# SVR_REVTT_1_3.net
KiCad netlist of a schematic drawn in Altium Designer
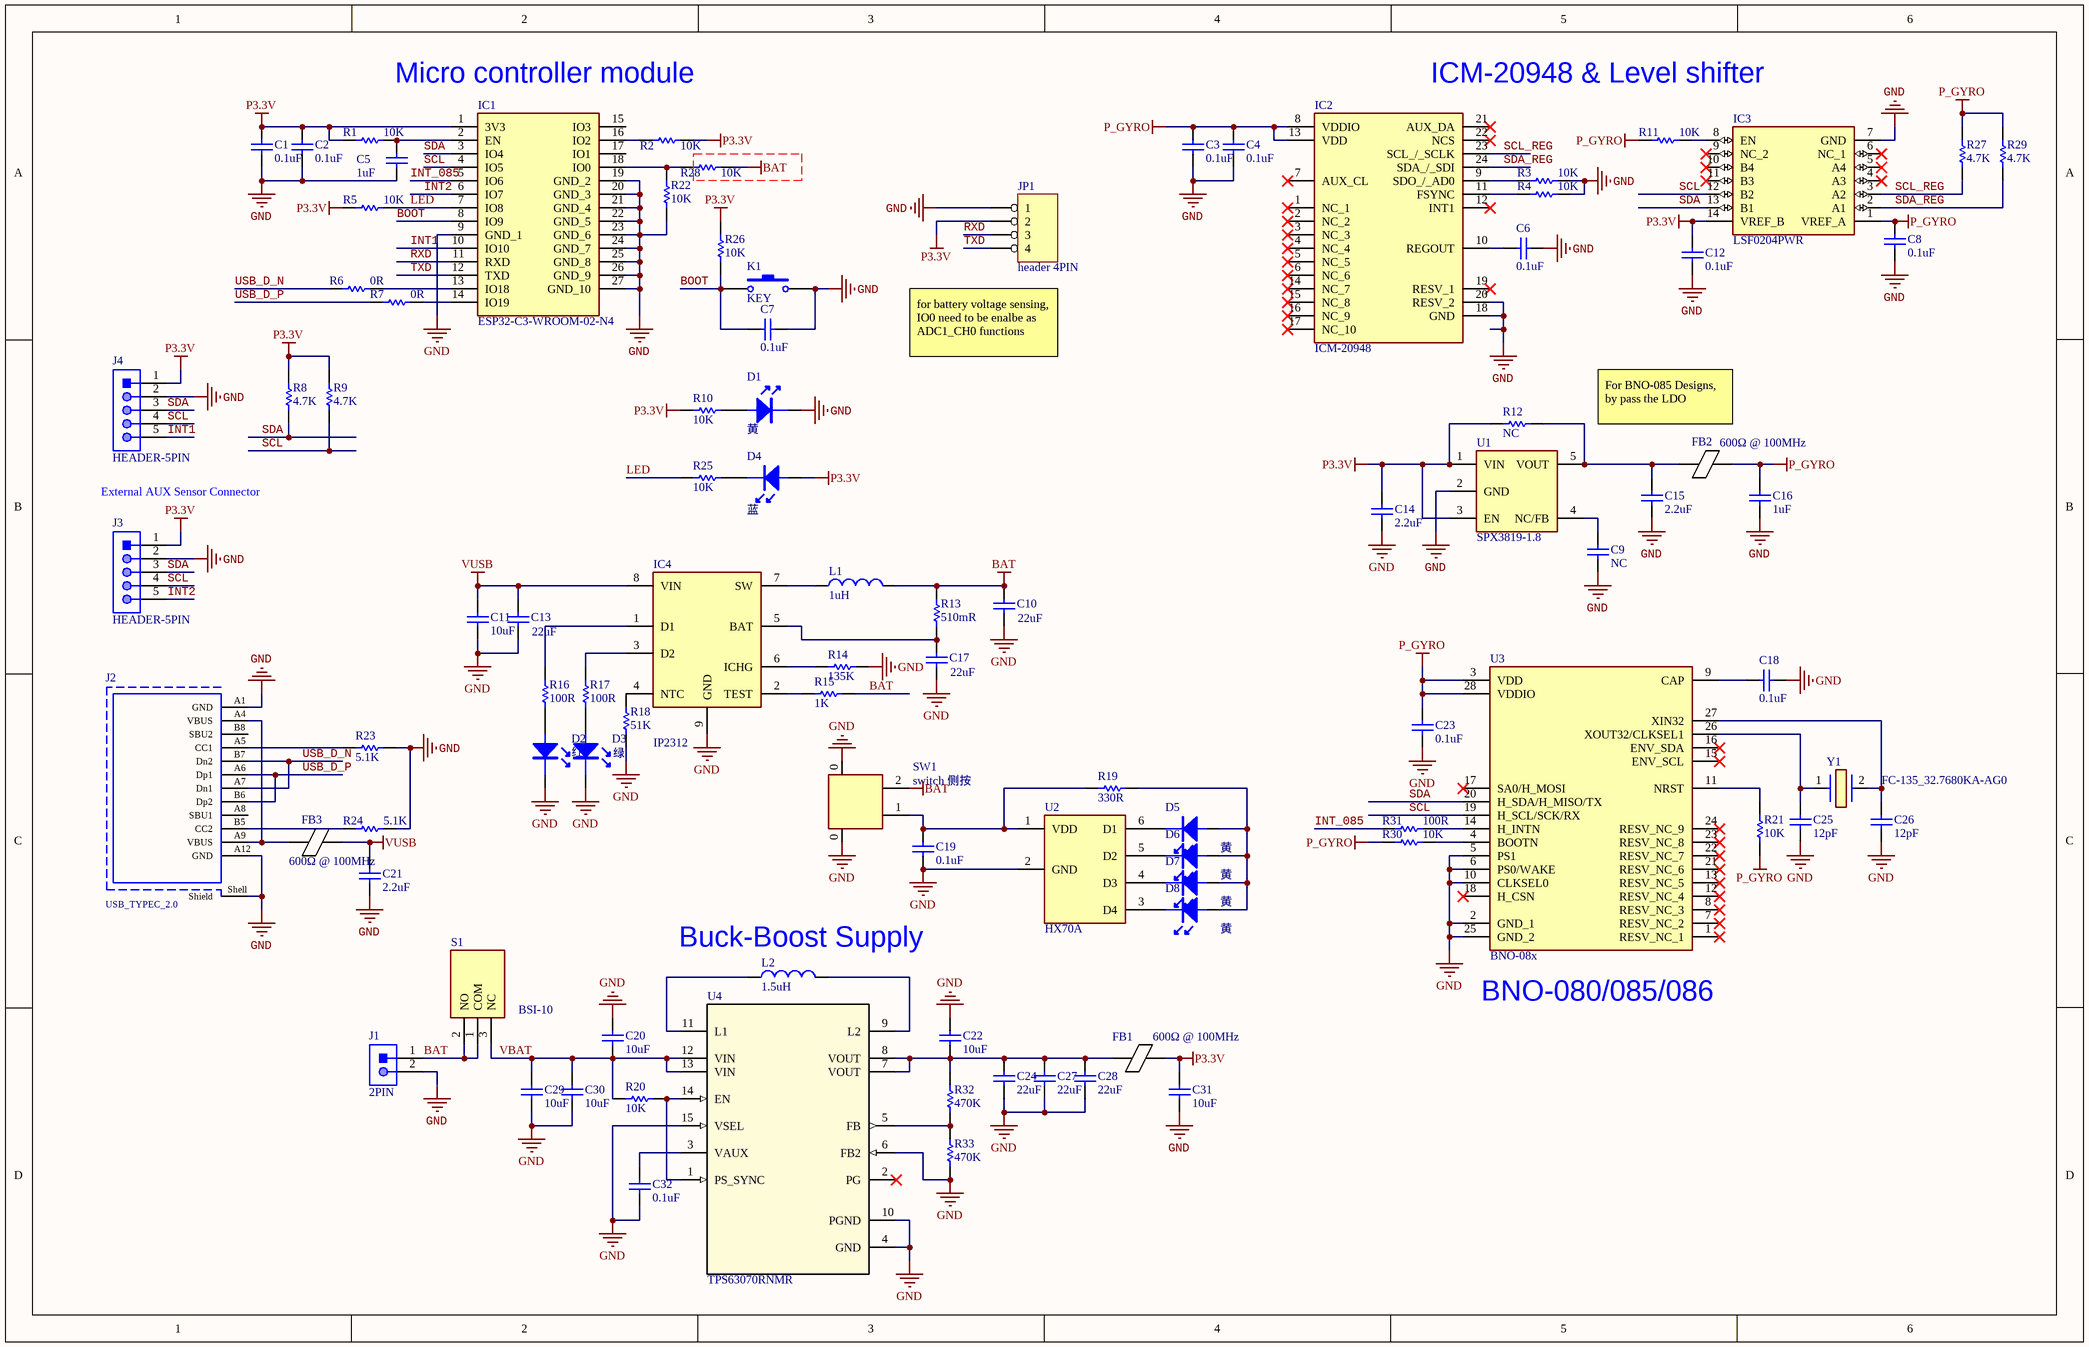
[diagram p0: SVR_REVTT_1.3.SchDoc]

(export (version "E")
  (design (tool "Eeschema 10.0.6"))
  (components
    (comp (ref "C1")
      (value "0.1uF")
      (footprint "0402L")
      (description "Capacitor")
      (fields (field (name "PUBLISHER") "Altium Limited"))
      (libsource (lib "My Footprint") (part "CAP"))
    )
    (comp (ref "C2")
      (value "0.1uF")
      (footprint "0402L")
      (description "Capacitor")
      (fields (field (name "PUBLISHER") "Altium Limited"))
      (libsource (lib "My Footprint") (part "CAP"))
    )
    (comp (ref "C3")
      (value "0.1uF")
      (footprint "0402L")
      (description "Capacitor")
      (fields (field (name "PUBLISHER") "Altium Limited"))
      (libsource (lib "My Footprint") (part "CAP"))
    )
    (comp (ref "C4")
      (value "0.1uF")
      (footprint "0402L")
      (description "Capacitor")
      (fields (field (name "PUBLISHER") "Altium Limited"))
      (libsource (lib "My Footprint") (part "CAP"))
    )
    (comp (ref "C5")
      (value "1uF")
      (footprint "0402L")
      (description "Capacitor")
      (fields (field (name "PUBLISHER") "Altium Limited"))
      (libsource (lib "My Footprint") (part "CAP"))
    )
    (comp (ref "C6")
      (value "0.1uF")
      (footprint "0402L")
      (description "Capacitor")
      (fields (field (name "PUBLISHER") "Altium Limited"))
      (libsource (lib "My Footprint") (part "CAP"))
    )
    (comp (ref "C7")
      (value "0.1uF")
      (footprint "0402L")
      (description "Capacitor")
      (fields (field (name "PUBLISHER") "Altium Limited"))
      (libsource (lib "My Footprint") (part "CAP"))
    )
    (comp (ref "C8")
      (value "0.1uF")
      (footprint "0402L")
      (description "Capacitor")
      (fields (field (name "PUBLISHER") "Altium Limited"))
      (libsource (lib "My Footprint") (part "CAP"))
    )
    (comp (ref "C9")
      (value "NC")
      (footprint "0603_C")
      (description "Capacitor")
      (fields (field (name "PUBLISHER") "Altium Limited"))
      (libsource (lib "My Footprint") (part "CAP"))
    )
    (comp (ref "C10")
      (value "22uF")
      (footprint "0805")
      (description "Capacitor")
      (fields (field (name "PUBLISHER") "Altium Limited"))
      (libsource (lib "My Footprint") (part "CAP"))
    )
    (comp (ref "C11")
      (value "10uF")
      (footprint "0805")
      (description "Capacitor")
      (fields (field (name "PUBLISHER") "Altium Limited"))
      (libsource (lib "My Footprint") (part "CAP"))
    )
    (comp (ref "C12")
      (value "0.1uF")
      (footprint "0402L")
      (description "Capacitor")
      (fields (field (name "PUBLISHER") "Altium Limited"))
      (libsource (lib "My Footprint") (part "CAP"))
    )
    (comp (ref "C13")
      (value "22uF")
      (footprint "0805")
      (description "Capacitor")
      (fields (field (name "PUBLISHER") "Altium Limited"))
      (libsource (lib "My Footprint") (part "CAP"))
    )
    (comp (ref "C14")
      (value "2.2uF")
      (footprint "0603_C")
      (description "Capacitor")
      (fields (field (name "PUBLISHER") "Altium Limited"))
      (libsource (lib "My Footprint") (part "CAP"))
    )
    (comp (ref "C15")
      (value "2.2uF")
      (footprint "0603_C")
      (description "Capacitor")
      (fields (field (name "PUBLISHER") "Altium Limited"))
      (libsource (lib "My Footprint") (part "CAP"))
    )
    (comp (ref "C16")
      (value "1uF")
      (footprint "0603_C")
      (description "Capacitor")
      (fields (field (name "PUBLISHER") "Altium Limited"))
      (libsource (lib "My Footprint") (part "CAP"))
    )
    (comp (ref "C17")
      (value "22uF")
      (footprint "0805")
      (description "Capacitor")
      (fields (field (name "PUBLISHER") "Altium Limited"))
      (libsource (lib "My Footprint") (part "CAP"))
    )
    (comp (ref "C18")
      (value "0.1uF")
      (footprint "0402L")
      (description "Capacitor")
      (fields (field (name "PUBLISHER") "Altium Limited"))
      (libsource (lib "My Footprint") (part "CAP"))
    )
    (comp (ref "C19")
      (value "0.1uF")
      (footprint "0402L")
      (description "Capacitor")
      (fields (field (name "PUBLISHER") "Altium Limited"))
      (libsource (lib "My Footprint") (part "CAP"))
    )
    (comp (ref "C20")
      (value "10uF")
      (footprint "0603_C")
      (description "Capacitor")
      (fields (field (name "PUBLISHER") "Altium Limited"))
      (libsource (lib "My Footprint") (part "CAP"))
    )
    (comp (ref "C21")
      (value "2.2uF")
      (footprint "0603_C")
      (description "Capacitor")
      (fields (field (name "PUBLISHER") "Altium Limited"))
      (libsource (lib "My Footprint") (part "CAP"))
    )
    (comp (ref "C22")
      (value "10uF")
      (footprint "0603_C")
      (description "Capacitor")
      (fields (field (name "PUBLISHER") "Altium Limited"))
      (libsource (lib "My Footprint") (part "CAP"))
    )
    (comp (ref "C23")
      (value "0.1uF")
      (footprint "0402L")
      (description "Capacitor")
      (fields (field (name "PUBLISHER") "Altium Limited"))
      (libsource (lib "My Footprint") (part "CAP"))
    )
    (comp (ref "C24")
      (value "22uF")
      (footprint "0805")
      (description "Capacitor")
      (fields (field (name "PUBLISHER") "Altium Limited"))
      (libsource (lib "My Footprint") (part "CAP"))
    )
    (comp (ref "C25")
      (value "12pF")
      (footprint "0402L")
      (description "Capacitor")
      (fields (field (name "PUBLISHER") "Altium Limited"))
      (libsource (lib "My Footprint") (part "CAP"))
    )
    (comp (ref "C26")
      (value "12pF")
      (footprint "0402L")
      (description "Capacitor")
      (fields (field (name "PUBLISHER") "Altium Limited"))
      (libsource (lib "My Footprint") (part "CAP"))
    )
    (comp (ref "C27")
      (value "22uF")
      (footprint "0805")
      (description "Capacitor")
      (fields (field (name "PUBLISHER") "Altium Limited"))
      (libsource (lib "My Footprint") (part "CAP"))
    )
    (comp (ref "C28")
      (value "22uF")
      (footprint "0805")
      (description "Capacitor")
      (fields (field (name "PUBLISHER") "Altium Limited"))
      (libsource (lib "My Footprint") (part "CAP"))
    )
    (comp (ref "C29")
      (value "10uF")
      (footprint "0805")
      (description "Capacitor")
      (fields (field (name "PUBLISHER") "Altium Limited"))
      (libsource (lib "My Footprint") (part "CAP"))
    )
    (comp (ref "C30")
      (value "10uF")
      (footprint "0805")
      (description "Capacitor")
      (fields (field (name "PUBLISHER") "Altium Limited"))
      (libsource (lib "My Footprint") (part "CAP"))
    )
    (comp (ref "C31")
      (value "10uF")
      (footprint "0805")
      (description "Capacitor")
      (fields (field (name "PUBLISHER") "Altium Limited"))
      (libsource (lib "My Footprint") (part "CAP"))
    )
    (comp (ref "C32")
      (value "0.1uF")
      (footprint "0402L")
      (description "Capacitor")
      (fields (field (name "PUBLISHER") "Altium Limited"))
      (libsource (lib "My Footprint") (part "CAP"))
    )
    (comp (ref "D1")
      (value "黄")
      (footprint "0603_LED")
      (description "LED 发光二极管")
      (libsource (lib "My Footprint") (part "LED"))
    )
    (comp (ref "D2")
      (value "红")
      (footprint "0603_LED")
      (description "LED 发光二极管")
      (libsource (lib "My Footprint") (part "LED"))
    )
    (comp (ref "D3")
      (value "绿")
      (footprint "0603_LED")
      (description "LED 发光二极管")
      (libsource (lib "My Footprint") (part "LED"))
    )
    (comp (ref "D4")
      (value "蓝")
      (footprint "0603_LED")
      (description "LED 发光二极管")
      (libsource (lib "") (part "LED_1"))
    )
    (comp (ref "D5")
      (value "黄")
      (footprint "0603_LED")
      (description "LED 发光二极管")
      (libsource (lib "My Footprint") (part "LED"))
    )
    (comp (ref "D6")
      (value "黄")
      (footprint "0603_LED")
      (description "LED 发光二极管")
      (libsource (lib "My Footprint") (part "LED"))
    )
    (comp (ref "D7")
      (value "黄")
      (footprint "0603_LED")
      (description "LED 发光二极管")
      (libsource (lib "My Footprint") (part "LED"))
    )
    (comp (ref "D8")
      (value "黄")
      (footprint "0603_LED")
      (description "LED 发光二极管")
      (libsource (lib "My Footprint") (part "LED"))
    )
    (comp (ref "FB1")
      (value "600Ω @ 100MHz")
      (footprint "0805")
      (description "磁珠 600Ω @ 100MHz")
      (libsource (lib "My Footprint") (part "FB"))
    )
    (comp (ref "FB2")
      (value "600Ω @ 100MHz")
      (footprint "0603")
      (description "磁珠 600Ω @ 100MHz")
      (libsource (lib "My Footprint") (part "FB"))
    )
    (comp (ref "FB3")
      (value "600Ω @ 100MHz")
      (footprint "0603")
      (description "磁珠 600Ω @ 100MHz")
      (libsource (lib "My Footprint") (part "FB"))
    )
    (comp (ref "IC1")
      (value "ESP32-C3-WROOM-02-N4")
      (footprint "SamacSys:ESP32C3WROOM02N4")
      (description "Integrated Circuit")
      (fields (field (name "MOUSER PART NUMBER") "356-ESP32C3WROOM02N4"))
      (libsource (lib "SamacSys") (part "ESP32-C3-WROOM-02-N4"))
    )
    (comp (ref "IC2")
      (value "ICM-20948")
      (footprint "SamacSys:QFN40P300X300X105-25N-D")
      (description "Integrated Circuit")
      (fields (field (name "MOUSER PART NUMBER") "410-ICM-20948"))
      (libsource (lib "SamacSys") (part "ICM-20948"))
    )
    (comp (ref "IC3")
      (value "LSF0204PWR")
      (footprint "SamacSys:SOP65P640X120-14N")
      (description "Integrated Circuit")
      (fields (field (name "MOUSER PART NUMBER") "595-LSF0204PWR"))
      (libsource (lib "SamacSys") (part "LSF0204PWR"))
    )
    (comp (ref "IC4")
      (value "IP2312")
      (footprint "SOIC-8N")
      (description "Integrated Circuit")
      (libsource (lib "SamacSys") (part "IP2312"))
    )
    (comp (ref "J1")
      (value "2PIN")
      (footprint "XH2.54-WI-2P")
      (libsource (lib "My Footprint") (part "HEADER 2PIN"))
    )
    (comp (ref "J2")
      (value "USB_TYPEC_2.0")
      (footprint "USB_TYPEC_2.0_Horizontal_SMT")
      (description "USB 3.1 Type C Receptacle WR-COM, Horizontal, SMT / THT")
      (fields (field (name "PART NUMBER") "632723300011") (field (name "PUBLISHER") "Wurth Elektronik"))
      (libsource (lib "RegenovoPcbLib") (part "USB_TYPEC_2.0"))
    )
    (comp (ref "J3")
      (value "HEADER-5PIN")
      (footprint "HEADER_5P_1.25_RT")
      (libsource (lib "My Footprint") (part "HEADER-5PIN"))
    )
    (comp (ref "J4")
      (value "HEADER-5PIN")
      (footprint "HEADER_5P_1.25_RT")
      (libsource (lib "My Footprint") (part "HEADER-5PIN"))
    )
    (comp (ref "JP1")
      (value "header 4PIN")
      (footprint "header4")
      (libsource (lib "My Footprint") (part "HEADER 4"))
    )
    (comp (ref "K1")
      (value "KEY")
      (footprint "KEY_2")
      (description "Switch")
      (fields (field (name "PUBLISHER") "Altium Limited"))
      (libsource (lib "My Footprint") (part "KEY_2"))
    )
    (comp (ref "L1")
      (value "1uH")
      (footprint "Inductor  SLO0650")
      (description "电感")
      (fields (field (name "Comment") "INDUCTOR") (field (name "PUBLISHER") "Altium Limited"))
      (libsource (lib "RegenovoPcbLib") (part "INDUCTOR"))
    )
    (comp (ref "L2")
      (value "1.5uH")
      (footprint "Inductor  SMNR4020")
      (description "电感")
      (fields (field (name "Comment") "INDUCTOR") (field (name "PUBLISHER") "Altium Limited"))
      (libsource (lib "RegenovoPcbLib") (part "INDUCTOR"))
    )
    (comp (ref "R1")
      (value "10K")
      (footprint "0402L")
      (description "Resistor")
      (fields (field (name "PUBLISHER") "Altium Limited"))
      (libsource (lib "My Footprint") (part "RES"))
    )
    (comp (ref "R2")
      (value "10K")
      (footprint "0402L")
      (description "Resistor")
      (fields (field (name "PUBLISHER") "Altium Limited"))
      (libsource (lib "My Footprint") (part "RES"))
    )
    (comp (ref "R3")
      (value "10K")
      (footprint "0402L")
      (description "Resistor")
      (fields (field (name "PUBLISHER") "Altium Limited"))
      (libsource (lib "My Footprint") (part "RES"))
    )
    (comp (ref "R4")
      (value "10K")
      (footprint "0402L")
      (description "Resistor")
      (fields (field (name "PUBLISHER") "Altium Limited"))
      (libsource (lib "My Footprint") (part "RES"))
    )
    (comp (ref "R5")
      (value "10K")
      (footprint "0402L")
      (description "Resistor")
      (fields (field (name "PUBLISHER") "Altium Limited"))
      (libsource (lib "My Footprint") (part "RES"))
    )
    (comp (ref "R6")
      (value "0R")
      (footprint "0402L")
      (description "Resistor")
      (fields (field (name "PUBLISHER") "Altium Limited"))
      (libsource (lib "My Footprint") (part "RES"))
    )
    (comp (ref "R7")
      (value "0R")
      (footprint "0402L")
      (description "Resistor")
      (fields (field (name "PUBLISHER") "Altium Limited"))
      (libsource (lib "My Footprint") (part "RES"))
    )
    (comp (ref "R8")
      (value "4.7K")
      (footprint "0402L")
      (description "Resistor")
      (fields (field (name "PUBLISHER") "Altium Limited"))
      (libsource (lib "My Footprint") (part "RES"))
    )
    (comp (ref "R9")
      (value "4.7K")
      (footprint "0402L")
      (description "Resistor")
      (fields (field (name "PUBLISHER") "Altium Limited"))
      (libsource (lib "My Footprint") (part "RES"))
    )
    (comp (ref "R10")
      (value "10K")
      (footprint "0402L")
      (description "Resistor")
      (fields (field (name "PUBLISHER") "Altium Limited"))
      (libsource (lib "My Footprint") (part "RES"))
    )
    (comp (ref "R11")
      (value "10K")
      (footprint "0402L")
      (description "Resistor")
      (fields (field (name "PUBLISHER") "Altium Limited"))
      (libsource (lib "My Footprint") (part "RES"))
    )
    (comp (ref "R12")
      (value "NC")
      (footprint "0603")
      (description "Resistor")
      (fields (field (name "PUBLISHER") "Altium Limited"))
      (libsource (lib "My Footprint") (part "RES"))
    )
    (comp (ref "R13")
      (value "510mR")
      (footprint "0603L")
      (description "Resistor")
      (fields (field (name "PUBLISHER") "Altium Limited"))
      (libsource (lib "My Footprint") (part "RES"))
    )
    (comp (ref "R14")
      (value "135K")
      (footprint "0402L")
      (description "Resistor")
      (fields (field (name "PUBLISHER") "Altium Limited"))
      (libsource (lib "My Footprint") (part "RES"))
    )
    (comp (ref "R15")
      (value "1K")
      (footprint "0402L")
      (description "Resistor")
      (fields (field (name "PUBLISHER") "Altium Limited"))
      (libsource (lib "My Footprint") (part "RES"))
    )
    (comp (ref "R16")
      (value "100R")
      (footprint "0402L")
      (description "Resistor")
      (fields (field (name "PUBLISHER") "Altium Limited"))
      (libsource (lib "My Footprint") (part "RES"))
    )
    (comp (ref "R17")
      (value "100R")
      (footprint "0402L")
      (description "Resistor")
      (fields (field (name "PUBLISHER") "Altium Limited"))
      (libsource (lib "My Footprint") (part "RES"))
    )
    (comp (ref "R18")
      (value "51K")
      (footprint "0402L")
      (description "Resistor")
      (fields (field (name "PUBLISHER") "Altium Limited"))
      (libsource (lib "My Footprint") (part "RES"))
    )
    (comp (ref "R19")
      (value "330R")
      (footprint "0603_R")
      (description "Resistor")
      (fields (field (name "PUBLISHER") "Altium Limited"))
      (libsource (lib "My Footprint") (part "RES"))
    )
    (comp (ref "R20")
      (value "10K")
      (footprint "0402L")
      (description "Resistor")
      (fields (field (name "PUBLISHER") "Altium Limited"))
      (libsource (lib "My Footprint") (part "RES"))
    )
    (comp (ref "R21")
      (value "10K")
      (footprint "0402L")
      (description "Resistor")
      (fields (field (name "PUBLISHER") "Altium Limited"))
      (libsource (lib "My Footprint") (part "RES"))
    )
    (comp (ref "R22")
      (value "10K")
      (footprint "0402L")
      (description "Resistor")
      (fields (field (name "PUBLISHER") "Altium Limited"))
      (libsource (lib "My Footprint") (part "RES"))
    )
    (comp (ref "R23")
      (value "5.1K")
      (footprint "0402L")
      (description "Resistor")
      (fields (field (name "PUBLISHER") "Altium Limited"))
      (libsource (lib "My Footprint") (part "RES"))
    )
    (comp (ref "R24")
      (value "5.1K")
      (footprint "0402L")
      (description "Resistor")
      (fields (field (name "PUBLISHER") "Altium Limited"))
      (libsource (lib "My Footprint") (part "RES"))
    )
    (comp (ref "R25")
      (value "10K")
      (footprint "0402L")
      (description "Resistor")
      (fields (field (name "PUBLISHER") "Altium Limited"))
      (libsource (lib "My Footprint") (part "RES"))
    )
    (comp (ref "R26")
      (value "10K")
      (footprint "0402L")
      (description "Resistor")
      (fields (field (name "PUBLISHER") "Altium Limited"))
      (libsource (lib "My Footprint") (part "RES"))
    )
    (comp (ref "R27")
      (value "4.7K")
      (footprint "0402L")
      (description "Resistor")
      (fields (field (name "PUBLISHER") "Altium Limited"))
      (libsource (lib "My Footprint") (part "RES"))
    )
    (comp (ref "R28")
      (value "10K")
      (footprint "0402L")
      (description "Resistor")
      (fields (field (name "PUBLISHER") "Altium Limited"))
      (libsource (lib "My Footprint") (part "RES"))
    )
    (comp (ref "R29")
      (value "4.7K")
      (footprint "0402L")
      (description "Resistor")
      (fields (field (name "PUBLISHER") "Altium Limited"))
      (libsource (lib "My Footprint") (part "RES"))
    )
    (comp (ref "R30")
      (value "10K")
      (footprint "0402L")
      (description "Resistor")
      (fields (field (name "PUBLISHER") "Altium Limited"))
      (libsource (lib "My Footprint") (part "RES"))
    )
    (comp (ref "R31")
      (value "100R")
      (footprint "0402L")
      (description "Resistor")
      (fields (field (name "PUBLISHER") "Altium Limited"))
      (libsource (lib "My Footprint") (part "RES"))
    )
    (comp (ref "R32")
      (value "470K")
      (footprint "0402L")
      (description "Resistor")
      (fields (field (name "PUBLISHER") "Altium Limited"))
      (libsource (lib "My Footprint") (part "RES"))
    )
    (comp (ref "R33")
      (value "470K")
      (footprint "0402L")
      (description "Resistor")
      (fields (field (name "PUBLISHER") "Altium Limited"))
      (libsource (lib "My Footprint") (part "RES"))
    )
    (comp (ref "S1")
      (value "BSI-10")
      (footprint "BSI10")
      (description "Switch")
      (libsource (lib "SamacSys") (part "BSI-10"))
    )
    (comp (ref "SW1")
      (value "switch 侧按")
      (footprint "TSW 3*6*4.3-S-W")
      (libsource (lib "SamacSys") (part "switch 侧按"))
    )
    (comp (ref "U1")
      (value "SPX3819-1.8")
      (footprint "SOT-23-5")
      (libsource (lib "My Footprint") (part "ADP150"))
    )
    (comp (ref "U2")
      (value "HX70A")
      (footprint "SOT95P250X110-6N")
      (description "单节锂电池电量指示芯片")
      (libsource (lib "SamacSys") (part "HX70A"))
    )
    (comp (ref "U3")
      (value "BNO-08x")
      (footprint "SamacSys:BNO085")
      (description "Accelerometer")
      (fields (field (name "MANUFACTURER_PART_NUMBER") "BNO085"))
      (libsource (lib "SamacSys") (part "BNO085"))
    )
    (comp (ref "U4")
      (value "TPS63070RNMR")
      (footprint "RNM0015A")
      (description "Imported")
      (fields (field (name "MANUFACTURER") "Texas Instruments"))
      (libsource (lib "SamacSys") (part "TPS63070RNMR"))
    )
    (comp (ref "Y1")
      (value "FC-135_32.7680KA-AG0")
      (footprint "SamacSys:FC135327680KAAG0")
      (description "Crystal or Oscillator")
      (fields
        (field (name "MANUFACTURER_PART_NUMBER") "FC-135 32.7680KA-AG0")
        (field (name "MOUSER PART NUMBER") "732-FC135-32.76KAAG0")
      )
      (libsource (lib "SamacSys") (part "FC-135_32.7680KA-AG0"))
    )
  )
  (nets
    (net (code "1") (name "/BOOT") (class "Default")
      (node (ref "C7") (pin "1") (pinfunction "1_1") (pintype "passive"))
      (node (ref "IC1") (pin "8") (pinfunction "IO9_8") (pintype "passive"))
      (node (ref "K1") (pin "1") (pinfunction "1_1") (pintype "passive"))
      (node (ref "R26") (pin "1") (pinfunction "1_1") (pintype "passive"))
    )
    (net (code "2") (name "/INT1") (class "Default")
      (node (ref "IC1") (pin "10") (pinfunction "IO10_10") (pintype "passive"))
      (node (ref "J4") (pin "5") (pinfunction "5_5") (pintype "passive"))
    )
    (net (code "3") (name "/INT2") (class "Default")
      (node (ref "IC1") (pin "6") (pinfunction "IO7_6") (pintype "passive"))
      (node (ref "J3") (pin "5") (pinfunction "5_5") (pintype "passive"))
    )
    (net (code "4") (name "/INT_085") (class "Default")
      (node (ref "IC1") (pin "5") (pinfunction "IO6_5") (pintype "passive"))
      (node (ref "R31") (pin "1") (pinfunction "1_1") (pintype "passive"))
    )
    (net (code "5") (name "/LED") (class "Default")
      (node (ref "IC1") (pin "7") (pinfunction "IO8_7") (pintype "passive"))
      (node (ref "R25") (pin "1") (pinfunction "1_1") (pintype "passive"))
      (node (ref "R5") (pin "2") (pinfunction "2_2") (pintype "passive"))
    )
    (net (code "6") (name "/RXD") (class "Default")
      (node (ref "IC1") (pin "11") (pinfunction "RXD_11") (pintype "passive"))
      (node (ref "JP1") (pin "3") (pinfunction "3_3") (pintype "passive"))
    )
    (net (code "7") (name "/SCL") (class "Default")
      (node (ref "IC1") (pin "4") (pinfunction "IO5_4") (pintype "passive"))
      (node (ref "IC3") (pin "12") (pinfunction "B2_12") (pintype "bidirectional"))
      (node (ref "J3") (pin "4") (pinfunction "4_4") (pintype "passive"))
      (node (ref "J4") (pin "4") (pinfunction "4_4") (pintype "passive"))
      (node (ref "R9") (pin "1") (pinfunction "1_1") (pintype "passive"))
      (node (ref "U3") (pin "19") (pinfunction "H_SCL/SCK/RX_19") (pintype "passive"))
    )
    (net (code "8") (name "/SCL_REG") (class "Default")
      (node (ref "IC2") (pin "23") (pinfunction "SCL_/_SCLK_23") (pintype "passive"))
      (node (ref "IC3") (pin "3") (pinfunction "A2_3") (pintype "bidirectional"))
      (node (ref "R27") (pin "1") (pinfunction "1_1") (pintype "passive"))
    )
    (net (code "9") (name "/SDA") (class "Default")
      (node (ref "IC1") (pin "3") (pinfunction "IO4_3") (pintype "passive"))
      (node (ref "IC3") (pin "13") (pinfunction "B1_13") (pintype "bidirectional"))
      (node (ref "J3") (pin "3") (pinfunction "3_3") (pintype "passive"))
      (node (ref "J4") (pin "3") (pinfunction "3_3") (pintype "passive"))
      (node (ref "R8") (pin "1") (pinfunction "1_1") (pintype "passive"))
      (node (ref "U3") (pin "20") (pinfunction "H_SDA/H_MISO/TX_20") (pintype "passive"))
    )
    (net (code "10") (name "/SDA_REG") (class "Default")
      (node (ref "IC2") (pin "24") (pinfunction "SDA_/_SDI_24") (pintype "passive"))
      (node (ref "IC3") (pin "2") (pinfunction "A1_2") (pintype "bidirectional"))
      (node (ref "R29") (pin "1") (pinfunction "1_1") (pintype "passive"))
    )
    (net (code "11") (name "/TXD") (class "Default")
      (node (ref "IC1") (pin "12") (pinfunction "TXD_12") (pintype "passive"))
      (node (ref "JP1") (pin "4") (pinfunction "4_4") (pintype "passive"))
    )
    (net (code "12") (name "/USB_D_N") (class "Default")
      (node (ref "J2") (pin "A7") (pinfunction "Dn1_A7") (pintype "passive"))
      (node (ref "J2") (pin "B7") (pinfunction "Dn2_B7") (pintype "passive"))
      (node (ref "R6") (pin "1") (pinfunction "1_1") (pintype "passive"))
    )
    (net (code "13") (name "/USB_D_P") (class "Default")
      (node (ref "J2") (pin "A6") (pinfunction "Dp1_A6") (pintype "passive"))
      (node (ref "J2") (pin "B6") (pinfunction "Dp2_B6") (pintype "passive"))
      (node (ref "R7") (pin "1") (pinfunction "1_1") (pintype "passive"))
    )
    (net (code "14") (name "/VBAT") (class "Default")
      (node (ref "C20") (pin "1") (pinfunction "1_1") (pintype "passive"))
      (node (ref "C29") (pin "2") (pinfunction "2_2") (pintype "passive"))
      (node (ref "C30") (pin "2") (pinfunction "2_2") (pintype "passive"))
      (node (ref "R20") (pin "1") (pinfunction "1_1") (pintype "passive"))
      (node (ref "S1") (pin "3") (pinfunction "NC_3") (pintype "passive"))
      (node (ref "U4") (pin "12") (pinfunction "VIN_12") (pintype "power_in"))
      (node (ref "U4") (pin "13") (pinfunction "VIN_13") (pintype "power_in"))
    )
    (net (code "15") (name "BAT") (class "Default")
      (node (ref "C10") (pin "2") (pinfunction "2_2") (pintype "passive"))
      (node (ref "J1") (pin "1") (pinfunction "1_1") (pintype "passive"))
      (node (ref "L1") (pin "2") (pinfunction "2_2") (pintype "passive"))
      (node (ref "R13") (pin "2") (pinfunction "2_2") (pintype "passive"))
      (node (ref "R15") (pin "2") (pinfunction "2_2") (pintype "passive"))
      (node (ref "R28") (pin "2") (pinfunction "2_2") (pintype "passive"))
      (node (ref "S1") (pin "1") (pinfunction "COM_1") (pintype "passive"))
      (node (ref "S1") (pin "2") (pinfunction "NO_2") (pintype "passive"))
      (node (ref "SW1") (pin "2") (pinfunction "2_2") (pintype "passive"))
    )
    (net (code "16") (name "GND") (class "Default")
      (node (ref "C1") (pin "1") (pinfunction "1_1") (pintype "passive"))
      (node (ref "C10") (pin "1") (pinfunction "1_1") (pintype "passive"))
      (node (ref "C11") (pin "1") (pinfunction "1_1") (pintype "passive"))
      (node (ref "C12") (pin "2") (pinfunction "2_2") (pintype "passive"))
      (node (ref "C13") (pin "1") (pinfunction "1_1") (pintype "passive"))
      (node (ref "C14") (pin "1") (pinfunction "1_1") (pintype "passive"))
      (node (ref "C15") (pin "1") (pinfunction "1_1") (pintype "passive"))
      (node (ref "C16") (pin "1") (pinfunction "1_1") (pintype "passive"))
      (node (ref "C17") (pin "1") (pinfunction "1_1") (pintype "passive"))
      (node (ref "C18") (pin "1") (pinfunction "1_1") (pintype "passive"))
      (node (ref "C19") (pin "1") (pinfunction "1_1") (pintype "passive"))
      (node (ref "C2") (pin "1") (pinfunction "1_1") (pintype "passive"))
      (node (ref "C20") (pin "2") (pinfunction "2_2") (pintype "passive"))
      (node (ref "C21") (pin "1") (pinfunction "1_1") (pintype "passive"))
      (node (ref "C22") (pin "2") (pinfunction "2_2") (pintype "passive"))
      (node (ref "C23") (pin "1") (pinfunction "1_1") (pintype "passive"))
      (node (ref "C24") (pin "2") (pinfunction "2_2") (pintype "passive"))
      (node (ref "C25") (pin "1") (pinfunction "1_1") (pintype "passive"))
      (node (ref "C26") (pin "1") (pinfunction "1_1") (pintype "passive"))
      (node (ref "C27") (pin "2") (pinfunction "2_2") (pintype "passive"))
      (node (ref "C28") (pin "2") (pinfunction "2_2") (pintype "passive"))
      (node (ref "C29") (pin "1") (pinfunction "1_1") (pintype "passive"))
      (node (ref "C3") (pin "2") (pinfunction "2_2") (pintype "passive"))
      (node (ref "C30") (pin "1") (pinfunction "1_1") (pintype "passive"))
      (node (ref "C31") (pin "1") (pinfunction "1_1") (pintype "passive"))
      (node (ref "C32") (pin "1") (pinfunction "1_1") (pintype "passive"))
      (node (ref "C4") (pin "2") (pinfunction "2_2") (pintype "passive"))
      (node (ref "C5") (pin "1") (pinfunction "1_1") (pintype "passive"))
      (node (ref "C6") (pin "1") (pinfunction "1_1") (pintype "passive"))
      (node (ref "C7") (pin "2") (pinfunction "2_2") (pintype "passive"))
      (node (ref "C8") (pin "2") (pinfunction "2_2") (pintype "passive"))
      (node (ref "C9") (pin "1") (pinfunction "1_1") (pintype "passive"))
      (node (ref "D1") (pin "1") (pinfunction "K_1") (pintype "passive"))
      (node (ref "D2") (pin "1") (pinfunction "K_1") (pintype "passive"))
      (node (ref "D3") (pin "1") (pinfunction "K_1") (pintype "passive"))
      (node (ref "IC1") (pin "19") (pinfunction "GND_2_19") (pintype "passive"))
      (node (ref "IC1") (pin "20") (pinfunction "GND_3_20") (pintype "passive"))
      (node (ref "IC1") (pin "21") (pinfunction "GND_4_21") (pintype "passive"))
      (node (ref "IC1") (pin "22") (pinfunction "GND_5_22") (pintype "passive"))
      (node (ref "IC1") (pin "23") (pinfunction "GND_6_23") (pintype "passive"))
      (node (ref "IC1") (pin "24") (pinfunction "GND_7_24") (pintype "passive"))
      (node (ref "IC1") (pin "25") (pinfunction "GND_8_25") (pintype "passive"))
      (node (ref "IC1") (pin "26") (pinfunction "GND_9_26") (pintype "passive"))
      (node (ref "IC1") (pin "27") (pinfunction "GND_10_27") (pintype "passive"))
      (node (ref "IC1") (pin "9") (pinfunction "GND_1_9") (pintype "passive"))
      (node (ref "IC2") (pin "18") (pinfunction "GND_18") (pintype "passive"))
      (node (ref "IC2") (pin "20") (pinfunction "RESV_2_20") (pintype "passive"))
      (node (ref "IC3") (pin "7") (pinfunction "GND_7") (pintype "power_in"))
      (node (ref "IC4") (pin "9") (pinfunction "GND_9") (pintype "passive"))
      (node (ref "J1") (pin "2") (pinfunction "2_2") (pintype "passive"))
      (node (ref "J2") (pin "A1") (pinfunction "GND_A1") (pintype "passive"))
      (node (ref "J2") (pin "A12") (pinfunction "GND_A12") (pintype "passive"))
      (node (ref "J2") (pin "Shell") (pinfunction "Shield_Shell") (pintype "passive"))
      (node (ref "J3") (pin "2") (pinfunction "2_2") (pintype "passive"))
      (node (ref "J4") (pin "2") (pinfunction "2_2") (pintype "passive"))
      (node (ref "JP1") (pin "1") (pinfunction "1_1") (pintype "passive"))
      (node (ref "K1") (pin "2") (pinfunction "2_2") (pintype "passive"))
      (node (ref "R14") (pin "2") (pinfunction "2_2") (pintype "passive"))
      (node (ref "R18") (pin "1") (pinfunction "1_1") (pintype "passive"))
      (node (ref "R22") (pin "1") (pinfunction "1_1") (pintype "passive"))
      (node (ref "R23") (pin "2") (pinfunction "2_2") (pintype "passive"))
      (node (ref "R24") (pin "2") (pinfunction "2_2") (pintype "passive"))
      (node (ref "R3") (pin "2") (pinfunction "2_2") (pintype "passive"))
      (node (ref "R33") (pin "1") (pinfunction "1_1") (pintype "passive"))
      (node (ref "R4") (pin "2") (pinfunction "2_2") (pintype "passive"))
      (node (ref "SW1") (pin "0") (pinfunction "0_0") (pintype "passive"))
      (node (ref "U1") (pin "2") (pinfunction "GND_2") (pintype "passive"))
      (node (ref "U2") (pin "2") (pinfunction "GND_2") (pintype "passive"))
      (node (ref "U3") (pin "10") (pinfunction "CLKSEL0_10") (pintype "passive"))
      (node (ref "U3") (pin "2") (pinfunction "GND_1_2") (pintype "passive"))
      (node (ref "U3") (pin "25") (pinfunction "GND_2_25") (pintype "passive"))
      (node (ref "U3") (pin "5") (pinfunction "PS1_5") (pintype "passive"))
      (node (ref "U3") (pin "6") (pinfunction "PS0/WAKE_6") (pintype "passive"))
      (node (ref "U4") (pin "10") (pinfunction "PGND_10") (pintype "power_in"))
      (node (ref "U4") (pin "15") (pinfunction "VSEL_15") (pintype "input"))
      (node (ref "U4") (pin "4") (pinfunction "GND_4") (pintype "power_in"))
      (node (ref "U4") (pin "6") (pinfunction "FB2_6") (pintype "input"))
    )
    (net (code "17") (name "Net-(C22-Pad1)") (class "Default")
      (node (ref "C22") (pin "1") (pinfunction "1_1") (pintype "passive"))
      (node (ref "C24") (pin "1") (pinfunction "1_1") (pintype "passive"))
      (node (ref "C27") (pin "1") (pinfunction "1_1") (pintype "passive"))
      (node (ref "C28") (pin "1") (pinfunction "1_1") (pintype "passive"))
      (node (ref "FB1") (pin "1") (pinfunction "1_1") (pintype "passive"))
      (node (ref "R32") (pin "2") (pinfunction "2_2") (pintype "passive"))
      (node (ref "U4") (pin "7") (pinfunction "VOUT_7") (pintype "power_in"))
      (node (ref "U4") (pin "8") (pinfunction "VOUT_8") (pintype "power_in"))
    )
    (net (code "18") (name "Net-(D1-A)") (class "Default")
      (node (ref "D1") (pin "2") (pinfunction "A_2") (pintype "passive"))
      (node (ref "R10") (pin "2") (pinfunction "2_2") (pintype "passive"))
    )
    (net (code "19") (name "Net-(D2-A)") (class "Default")
      (node (ref "D2") (pin "2") (pinfunction "A_2") (pintype "passive"))
      (node (ref "R16") (pin "1") (pinfunction "1_1") (pintype "passive"))
    )
    (net (code "20") (name "Net-(D3-A)") (class "Default")
      (node (ref "D3") (pin "2") (pinfunction "A_2") (pintype "passive"))
      (node (ref "R17") (pin "1") (pinfunction "1_1") (pintype "passive"))
    )
    (net (code "21") (name "Net-(D4-A-Pad2)") (class "Default")
      (node (ref "D4") (pin "2") (pinfunction "A_2") (pintype "passive"))
      (node (ref "R25") (pin "2") (pinfunction "2_2") (pintype "passive"))
    )
    (net (code "22") (name "Net-(D5-A)") (class "Default")
      (node (ref "D5") (pin "2") (pinfunction "A_2") (pintype "passive"))
      (node (ref "D6") (pin "2") (pinfunction "A_2") (pintype "passive"))
      (node (ref "D7") (pin "2") (pinfunction "A_2") (pintype "passive"))
      (node (ref "D8") (pin "2") (pinfunction "A_2") (pintype "passive"))
      (node (ref "R19") (pin "2") (pinfunction "2_2") (pintype "passive"))
    )
    (net (code "23") (name "Net-(D5-K)") (class "Default")
      (node (ref "D5") (pin "1") (pinfunction "K_1") (pintype "passive"))
      (node (ref "U2") (pin "6") (pinfunction "D1_6") (pintype "passive"))
    )
    (net (code "24") (name "Net-(D6-K)") (class "Default")
      (node (ref "D6") (pin "1") (pinfunction "K_1") (pintype "passive"))
      (node (ref "U2") (pin "5") (pinfunction "D2_5") (pintype "passive"))
    )
    (net (code "25") (name "Net-(D7-K)") (class "Default")
      (node (ref "D7") (pin "1") (pinfunction "K_1") (pintype "passive"))
      (node (ref "U2") (pin "4") (pinfunction "D3_4") (pintype "passive"))
    )
    (net (code "26") (name "Net-(D8-K)") (class "Default")
      (node (ref "D8") (pin "1") (pinfunction "K_1") (pintype "passive"))
      (node (ref "U2") (pin "3") (pinfunction "D4_3") (pintype "passive"))
    )
    (net (code "27") (name "Net-(FB3-Pad1)") (class "Default")
      (node (ref "FB3") (pin "1") (pinfunction "1_1") (pintype "passive"))
      (node (ref "J2") (pin "A4") (pinfunction "VBUS_A4") (pintype "passive"))
      (node (ref "J2") (pin "A9") (pinfunction "VBUS_A9") (pintype "passive"))
    )
    (net (code "28") (name "Net-(IC1-EN)") (class "Default")
      (node (ref "C5") (pin "2") (pinfunction "2_2") (pintype "passive"))
      (node (ref "IC1") (pin "2") (pinfunction "EN_2") (pintype "passive"))
      (node (ref "R1") (pin "2") (pinfunction "2_2") (pintype "passive"))
    )
    (net (code "29") (name "Net-(IC1-IO0)") (class "Default")
      (node (ref "IC1") (pin "18") (pinfunction "IO0_18") (pintype "passive"))
      (node (ref "R22") (pin "2") (pinfunction "2_2") (pintype "passive"))
      (node (ref "R28") (pin "1") (pinfunction "1_1") (pintype "passive"))
    )
    (net (code "30") (name "Net-(IC1-IO2)") (class "Default")
      (node (ref "IC1") (pin "16") (pinfunction "IO2_16") (pintype "passive"))
      (node (ref "R2") (pin "1") (pinfunction "1_1") (pintype "passive"))
    )
    (net (code "31") (name "Net-(IC1-IO18)") (class "Default")
      (node (ref "IC1") (pin "13") (pinfunction "IO18_13") (pintype "passive"))
      (node (ref "R6") (pin "2") (pinfunction "2_2") (pintype "passive"))
    )
    (net (code "32") (name "Net-(IC1-IO19)") (class "Default")
      (node (ref "IC1") (pin "14") (pinfunction "IO19_14") (pintype "passive"))
      (node (ref "R7") (pin "2") (pinfunction "2_2") (pintype "passive"))
    )
    (net (code "33") (name "Net-(IC2-FSYNC)") (class "Default")
      (node (ref "IC2") (pin "11") (pinfunction "FSYNC_11") (pintype "passive"))
      (node (ref "R4") (pin "1") (pinfunction "1_1") (pintype "passive"))
    )
    (net (code "34") (name "Net-(IC2-REGOUT)") (class "Default")
      (node (ref "C6") (pin "2") (pinfunction "2_2") (pintype "passive"))
      (node (ref "IC2") (pin "10") (pinfunction "REGOUT_10") (pintype "passive"))
    )
    (net (code "35") (name "Net-(IC2-SDO_{slash}_AD0)") (class "Default")
      (node (ref "IC2") (pin "9") (pinfunction "SDO_/_AD0_9") (pintype "passive"))
      (node (ref "R3") (pin "1") (pinfunction "1_1") (pintype "passive"))
    )
    (net (code "36") (name "Net-(IC3-EN)") (class "Default")
      (node (ref "IC3") (pin "8") (pinfunction "EN_8") (pintype "bidirectional"))
      (node (ref "R11") (pin "2") (pinfunction "2_2") (pintype "passive"))
    )
    (net (code "37") (name "Net-(IC4-BAT)") (class "Default")
      (node (ref "C17") (pin "2") (pinfunction "2_2") (pintype "passive"))
      (node (ref "IC4") (pin "5") (pinfunction "BAT_5") (pintype "passive"))
      (node (ref "R13") (pin "1") (pinfunction "1_1") (pintype "passive"))
    )
    (net (code "38") (name "Net-(IC4-D1)") (class "Default")
      (node (ref "IC4") (pin "1") (pinfunction "D1_1") (pintype "passive"))
      (node (ref "R16") (pin "2") (pinfunction "2_2") (pintype "passive"))
    )
    (net (code "39") (name "Net-(IC4-D2)") (class "Default")
      (node (ref "IC4") (pin "3") (pinfunction "D2_3") (pintype "passive"))
      (node (ref "R17") (pin "2") (pinfunction "2_2") (pintype "passive"))
    )
    (net (code "40") (name "Net-(IC4-ICHG)") (class "Default")
      (node (ref "IC4") (pin "6") (pinfunction "ICHG_6") (pintype "passive"))
      (node (ref "R14") (pin "1") (pinfunction "1_1") (pintype "passive"))
    )
    (net (code "41") (name "Net-(IC4-NTC)") (class "Default")
      (node (ref "IC4") (pin "4") (pinfunction "NTC_4") (pintype "passive"))
      (node (ref "R18") (pin "2") (pinfunction "2_2") (pintype "passive"))
    )
    (net (code "42") (name "Net-(IC4-SW)") (class "Default")
      (node (ref "IC4") (pin "7") (pinfunction "SW_7") (pintype "passive"))
      (node (ref "L1") (pin "1") (pinfunction "1_1") (pintype "passive"))
    )
    (net (code "43") (name "Net-(IC4-TEST)") (class "Default")
      (node (ref "IC4") (pin "2") (pinfunction "TEST_2") (pintype "passive"))
      (node (ref "R15") (pin "1") (pinfunction "1_1") (pintype "passive"))
    )
    (net (code "44") (name "Net-(J2-CC1)") (class "Default")
      (node (ref "J2") (pin "A5") (pinfunction "CC1_A5") (pintype "passive"))
      (node (ref "R23") (pin "1") (pinfunction "1_1") (pintype "passive"))
    )
    (net (code "45") (name "Net-(J2-CC2)") (class "Default")
      (node (ref "J2") (pin "B5") (pinfunction "CC2_B5") (pintype "passive"))
      (node (ref "R24") (pin "1") (pinfunction "1_1") (pintype "passive"))
    )
    (net (code "46") (name "Net-(U1-NC{slash}FB)") (class "Default")
      (node (ref "C9") (pin "2") (pinfunction "2_2") (pintype "passive"))
      (node (ref "U1") (pin "4") (pinfunction "NC/FB_4") (pintype "passive"))
    )
    (net (code "47") (name "Net-(U1-VOUT)") (class "Default")
      (node (ref "C15") (pin "2") (pinfunction "2_2") (pintype "passive"))
      (node (ref "FB2") (pin "1") (pinfunction "1_1") (pintype "passive"))
      (node (ref "R12") (pin "1") (pinfunction "1_1") (pintype "passive"))
      (node (ref "U1") (pin "5") (pinfunction "VOUT_5") (pintype "passive"))
    )
    (net (code "48") (name "Net-(U2-VDD)") (class "Default")
      (node (ref "C19") (pin "2") (pinfunction "2_2") (pintype "passive"))
      (node (ref "R19") (pin "1") (pinfunction "1_1") (pintype "passive"))
      (node (ref "SW1") (pin "1") (pinfunction "1_1") (pintype "passive"))
      (node (ref "U2") (pin "1") (pinfunction "VDD_1") (pintype "passive"))
    )
    (net (code "49") (name "Net-(U3-BOOTN)") (class "Default")
      (node (ref "R30") (pin "2") (pinfunction "2_2") (pintype "passive"))
      (node (ref "U3") (pin "4") (pinfunction "BOOTN_4") (pintype "passive"))
    )
    (net (code "50") (name "Net-(U3-CAP)") (class "Default")
      (node (ref "C18") (pin "2") (pinfunction "2_2") (pintype "passive"))
      (node (ref "U3") (pin "9") (pinfunction "CAP_9") (pintype "passive"))
    )
    (net (code "51") (name "Net-(U3-H_INTN)") (class "Default")
      (node (ref "R31") (pin "2") (pinfunction "2_2") (pintype "passive"))
      (node (ref "U3") (pin "14") (pinfunction "H_INTN_14") (pintype "passive"))
    )
    (net (code "52") (name "Net-(U3-NRST)") (class "Default")
      (node (ref "R21") (pin "2") (pinfunction "2_2") (pintype "passive"))
      (node (ref "U3") (pin "11") (pinfunction "NRST_11") (pintype "passive"))
    )
    (net (code "53") (name "Net-(U3-XIN32)") (class "Default")
      (node (ref "C26") (pin "2") (pinfunction "2_2") (pintype "passive"))
      (node (ref "U3") (pin "27") (pinfunction "XIN32_27") (pintype "passive"))
      (node (ref "Y1") (pin "2") (pinfunction "CRYSTAL_2_2") (pintype "passive"))
    )
    (net (code "54") (name "Net-(U3-XOUT32{slash}CLKSEL1)") (class "Default")
      (node (ref "C25") (pin "2") (pinfunction "2_2") (pintype "passive"))
      (node (ref "U3") (pin "26") (pinfunction "XOUT32/CLKSEL1_26") (pintype "passive"))
      (node (ref "Y1") (pin "1") (pinfunction "1_1") (pintype "passive"))
    )
    (net (code "55") (name "Net-(U4-EN)") (class "Default")
      (node (ref "R20") (pin "2") (pinfunction "2_2") (pintype "passive"))
      (node (ref "U4") (pin "1") (pinfunction "PS_SYNC_1") (pintype "input"))
      (node (ref "U4") (pin "14") (pinfunction "EN_14") (pintype "input"))
    )
    (net (code "56") (name "Net-(U4-FB)") (class "Default")
      (node (ref "R32") (pin "1") (pinfunction "1_1") (pintype "passive"))
      (node (ref "R33") (pin "2") (pinfunction "2_2") (pintype "passive"))
      (node (ref "U4") (pin "5") (pinfunction "FB_5") (pintype "output"))
    )
    (net (code "57") (name "Net-(U4-L1)") (class "Default")
      (node (ref "L2") (pin "1") (pinfunction "1_1") (pintype "passive"))
      (node (ref "U4") (pin "11") (pinfunction "L1_11") (pintype "passive"))
    )
    (net (code "58") (name "Net-(U4-L2)") (class "Default")
      (node (ref "L2") (pin "2") (pinfunction "2_2") (pintype "passive"))
      (node (ref "U4") (pin "9") (pinfunction "L2_9") (pintype "passive"))
    )
    (net (code "59") (name "Net-(U4-VAUX)") (class "Default")
      (node (ref "C32") (pin "2") (pinfunction "2_2") (pintype "passive"))
      (node (ref "U4") (pin "3") (pinfunction "VAUX_3") (pintype "passive"))
    )
    (net (code "60") (name "P3.3V") (class "Default")
      (node (ref "C1") (pin "2") (pinfunction "2_2") (pintype "passive"))
      (node (ref "C12") (pin "1") (pinfunction "1_1") (pintype "passive"))
      (node (ref "C14") (pin "2") (pinfunction "2_2") (pintype "passive"))
      (node (ref "C2") (pin "2") (pinfunction "2_2") (pintype "passive"))
      (node (ref "C31") (pin "2") (pinfunction "2_2") (pintype "passive"))
      (node (ref "D4") (pin "1") (pinfunction "A_1") (pintype "passive"))
      (node (ref "FB1") (pin "2") (pinfunction "2_2") (pintype "passive"))
      (node (ref "IC1") (pin "1") (pinfunction "3V3_1") (pintype "passive"))
      (node (ref "IC3") (pin "14") (pinfunction "VREF_B_14") (pintype "power_in"))
      (node (ref "J3") (pin "1") (pinfunction "1_1") (pintype "passive"))
      (node (ref "J4") (pin "1") (pinfunction "1_1") (pintype "passive"))
      (node (ref "JP1") (pin "2") (pinfunction "2_2") (pintype "passive"))
      (node (ref "R1") (pin "1") (pinfunction "1_1") (pintype "passive"))
      (node (ref "R10") (pin "1") (pinfunction "1_1") (pintype "passive"))
      (node (ref "R12") (pin "2") (pinfunction "2_2") (pintype "passive"))
      (node (ref "R2") (pin "2") (pinfunction "2_2") (pintype "passive"))
      (node (ref "R26") (pin "2") (pinfunction "2_2") (pintype "passive"))
      (node (ref "R5") (pin "1") (pinfunction "1_1") (pintype "passive"))
      (node (ref "R8") (pin "2") (pinfunction "2_2") (pintype "passive"))
      (node (ref "R9") (pin "2") (pinfunction "2_2") (pintype "passive"))
      (node (ref "U1") (pin "1") (pinfunction "VIN_1") (pintype "passive"))
      (node (ref "U1") (pin "3") (pinfunction "EN_3") (pintype "passive"))
    )
    (net (code "61") (name "P_GYRO") (class "Default")
      (node (ref "C16") (pin "2") (pinfunction "2_2") (pintype "passive"))
      (node (ref "C23") (pin "2") (pinfunction "2_2") (pintype "passive"))
      (node (ref "C3") (pin "1") (pinfunction "1_1") (pintype "passive"))
      (node (ref "C4") (pin "1") (pinfunction "1_1") (pintype "passive"))
      (node (ref "C8") (pin "1") (pinfunction "1_1") (pintype "passive"))
      (node (ref "FB2") (pin "2") (pinfunction "2_2") (pintype "passive"))
      (node (ref "IC2") (pin "13") (pinfunction "VDD_13") (pintype "passive"))
      (node (ref "IC2") (pin "8") (pinfunction "VDDIO_8") (pintype "passive"))
      (node (ref "IC3") (pin "1") (pinfunction "VREF_A_1") (pintype "power_in"))
      (node (ref "R11") (pin "1") (pinfunction "1_1") (pintype "passive"))
      (node (ref "R21") (pin "1") (pinfunction "1_1") (pintype "passive"))
      (node (ref "R27") (pin "2") (pinfunction "2_2") (pintype "passive"))
      (node (ref "R29") (pin "2") (pinfunction "2_2") (pintype "passive"))
      (node (ref "R30") (pin "1") (pinfunction "1_1") (pintype "passive"))
      (node (ref "U3") (pin "28") (pinfunction "VDDIO_28") (pintype "passive"))
      (node (ref "U3") (pin "3") (pinfunction "VDD_3") (pintype "passive"))
    )
    (net (code "62") (name "VUSB") (class "Default")
      (node (ref "C11") (pin "2") (pinfunction "2_2") (pintype "passive"))
      (node (ref "C13") (pin "2") (pinfunction "2_2") (pintype "passive"))
      (node (ref "C21") (pin "2") (pinfunction "2_2") (pintype "passive"))
      (node (ref "FB3") (pin "2") (pinfunction "2_2") (pintype "passive"))
      (node (ref "IC4") (pin "8") (pinfunction "VIN_8") (pintype "passive"))
    )
    (net (code "63") (name "unconnected-(IC1-IO1-Pad17)") (class "Default")
      (node (ref "IC1") (pin "17") (pinfunction "IO1_17") (pintype "passive"))
    )
    (net (code "64") (name "unconnected-(IC1-IO3-Pad15)") (class "Default")
      (node (ref "IC1") (pin "15") (pinfunction "IO3_15") (pintype "passive"))
    )
    (net (code "65") (name "unconnected-(IC2-AUX_CL-Pad7)") (class "Default")
      (node (ref "IC2") (pin "7") (pinfunction "AUX_CL_7") (pintype "passive+no_connect"))
    )
    (net (code "66") (name "unconnected-(IC2-AUX_DA-Pad21)") (class "Default")
      (node (ref "IC2") (pin "21") (pinfunction "AUX_DA_21") (pintype "passive+no_connect"))
    )
    (net (code "67") (name "unconnected-(IC2-INT1-Pad12)") (class "Default")
      (node (ref "IC2") (pin "12") (pinfunction "INT1_12") (pintype "passive+no_connect"))
    )
    (net (code "68") (name "unconnected-(IC2-NCS-Pad22)") (class "Default")
      (node (ref "IC2") (pin "22") (pinfunction "NCS_22") (pintype "passive+no_connect"))
    )
    (net (code "69") (name "unconnected-(IC2-NC_1-Pad1)") (class "Default")
      (node (ref "IC2") (pin "1") (pinfunction "NC_1_1") (pintype "passive+no_connect"))
    )
    (net (code "70") (name "unconnected-(IC2-NC_2-Pad2)") (class "Default")
      (node (ref "IC2") (pin "2") (pinfunction "NC_2_2") (pintype "passive+no_connect"))
    )
    (net (code "71") (name "unconnected-(IC2-NC_3-Pad3)") (class "Default")
      (node (ref "IC2") (pin "3") (pinfunction "NC_3_3") (pintype "passive+no_connect"))
    )
    (net (code "72") (name "unconnected-(IC2-NC_4-Pad4)") (class "Default")
      (node (ref "IC2") (pin "4") (pinfunction "NC_4_4") (pintype "passive+no_connect"))
    )
    (net (code "73") (name "unconnected-(IC2-NC_5-Pad5)") (class "Default")
      (node (ref "IC2") (pin "5") (pinfunction "NC_5_5") (pintype "passive+no_connect"))
    )
    (net (code "74") (name "unconnected-(IC2-NC_6-Pad6)") (class "Default")
      (node (ref "IC2") (pin "6") (pinfunction "NC_6_6") (pintype "passive+no_connect"))
    )
    (net (code "75") (name "unconnected-(IC2-NC_7-Pad14)") (class "Default")
      (node (ref "IC2") (pin "14") (pinfunction "NC_7_14") (pintype "passive+no_connect"))
    )
    (net (code "76") (name "unconnected-(IC2-NC_8-Pad15)") (class "Default")
      (node (ref "IC2") (pin "15") (pinfunction "NC_8_15") (pintype "passive+no_connect"))
    )
    (net (code "77") (name "unconnected-(IC2-NC_9-Pad16)") (class "Default")
      (node (ref "IC2") (pin "16") (pinfunction "NC_9_16") (pintype "passive+no_connect"))
    )
    (net (code "78") (name "unconnected-(IC2-NC_10-Pad17)") (class "Default")
      (node (ref "IC2") (pin "17") (pinfunction "NC_10_17") (pintype "passive+no_connect"))
    )
    (net (code "79") (name "unconnected-(IC2-RESV_1-Pad19)") (class "Default")
      (node (ref "IC2") (pin "19") (pinfunction "RESV_1_19") (pintype "passive+no_connect"))
    )
    (net (code "80") (name "unconnected-(IC3-A3-Pad4)") (class "Default")
      (node (ref "IC3") (pin "4") (pinfunction "A3_4") (pintype "bidirectional+no_connect"))
    )
    (net (code "81") (name "unconnected-(IC3-A4-Pad5)") (class "Default")
      (node (ref "IC3") (pin "5") (pinfunction "A4_5") (pintype "bidirectional+no_connect"))
    )
    (net (code "82") (name "unconnected-(IC3-B3-Pad11)") (class "Default")
      (node (ref "IC3") (pin "11") (pinfunction "B3_11") (pintype "bidirectional+no_connect"))
    )
    (net (code "83") (name "unconnected-(IC3-B4-Pad10)") (class "Default")
      (node (ref "IC3") (pin "10") (pinfunction "B4_10") (pintype "bidirectional+no_connect"))
    )
    (net (code "84") (name "unconnected-(IC3-NC_1-Pad6)") (class "Default")
      (node (ref "IC3") (pin "6") (pinfunction "NC_1_6") (pintype "bidirectional+no_connect"))
    )
    (net (code "85") (name "unconnected-(IC3-NC_2-Pad9)") (class "Default")
      (node (ref "IC3") (pin "9") (pinfunction "NC_2_9") (pintype "bidirectional+no_connect"))
    )
    (net (code "86") (name "unconnected-(J2-SBU1-PadA8)") (class "Default")
      (node (ref "J2") (pin "A8") (pinfunction "SBU1_A8") (pintype "passive"))
    )
    (net (code "87") (name "unconnected-(J2-SBU2-PadB8)") (class "Default")
      (node (ref "J2") (pin "B8") (pinfunction "SBU2_B8") (pintype "passive"))
    )
    (net (code "88") (name "unconnected-(U3-ENV_SCL-Pad15)") (class "Default")
      (node (ref "U3") (pin "15") (pinfunction "ENV_SCL_15") (pintype "passive+no_connect"))
    )
    (net (code "89") (name "unconnected-(U3-ENV_SDA-Pad16)") (class "Default")
      (node (ref "U3") (pin "16") (pinfunction "ENV_SDA_16") (pintype "passive+no_connect"))
    )
    (net (code "90") (name "unconnected-(U3-H_CSN-Pad18)") (class "Default")
      (node (ref "U3") (pin "18") (pinfunction "H_CSN_18") (pintype "passive+no_connect"))
    )
    (net (code "91") (name "unconnected-(U3-RESV_NC_1-Pad1)") (class "Default")
      (node (ref "U3") (pin "1") (pinfunction "RESV_NC_1_1") (pintype "passive+no_connect"))
    )
    (net (code "92") (name "unconnected-(U3-RESV_NC_2-Pad7)") (class "Default")
      (node (ref "U3") (pin "7") (pinfunction "RESV_NC_2_7") (pintype "passive+no_connect"))
    )
    (net (code "93") (name "unconnected-(U3-RESV_NC_3-Pad8)") (class "Default")
      (node (ref "U3") (pin "8") (pinfunction "RESV_NC_3_8") (pintype "passive+no_connect"))
    )
    (net (code "94") (name "unconnected-(U3-RESV_NC_4-Pad12)") (class "Default")
      (node (ref "U3") (pin "12") (pinfunction "RESV_NC_4_12") (pintype "passive+no_connect"))
    )
    (net (code "95") (name "unconnected-(U3-RESV_NC_5-Pad13)") (class "Default")
      (node (ref "U3") (pin "13") (pinfunction "RESV_NC_5_13") (pintype "passive+no_connect"))
    )
    (net (code "96") (name "unconnected-(U3-RESV_NC_6-Pad21)") (class "Default")
      (node (ref "U3") (pin "21") (pinfunction "RESV_NC_6_21") (pintype "passive+no_connect"))
    )
    (net (code "97") (name "unconnected-(U3-RESV_NC_7-Pad22)") (class "Default")
      (node (ref "U3") (pin "22") (pinfunction "RESV_NC_7_22") (pintype "passive+no_connect"))
    )
    (net (code "98") (name "unconnected-(U3-RESV_NC_8-Pad23)") (class "Default")
      (node (ref "U3") (pin "23") (pinfunction "RESV_NC_8_23") (pintype "passive+no_connect"))
    )
    (net (code "99") (name "unconnected-(U3-RESV_NC_9-Pad24)") (class "Default")
      (node (ref "U3") (pin "24") (pinfunction "RESV_NC_9_24") (pintype "passive+no_connect"))
    )
    (net (code "100") (name "unconnected-(U3-SA0{slash}H_MOSI-Pad17)") (class "Default")
      (node (ref "U3") (pin "17") (pinfunction "SA0/H_MOSI_17") (pintype "passive+no_connect"))
    )
    (net (code "101") (name "unconnected-(U4-PG-Pad2)") (class "Default")
      (node (ref "U4") (pin "2") (pinfunction "PG_2") (pintype "open_collector+no_connect"))
    )
  )
)
